# 08_-_CPU_USB.net
KiCad netlist of a schematic drawn in Altium Designer
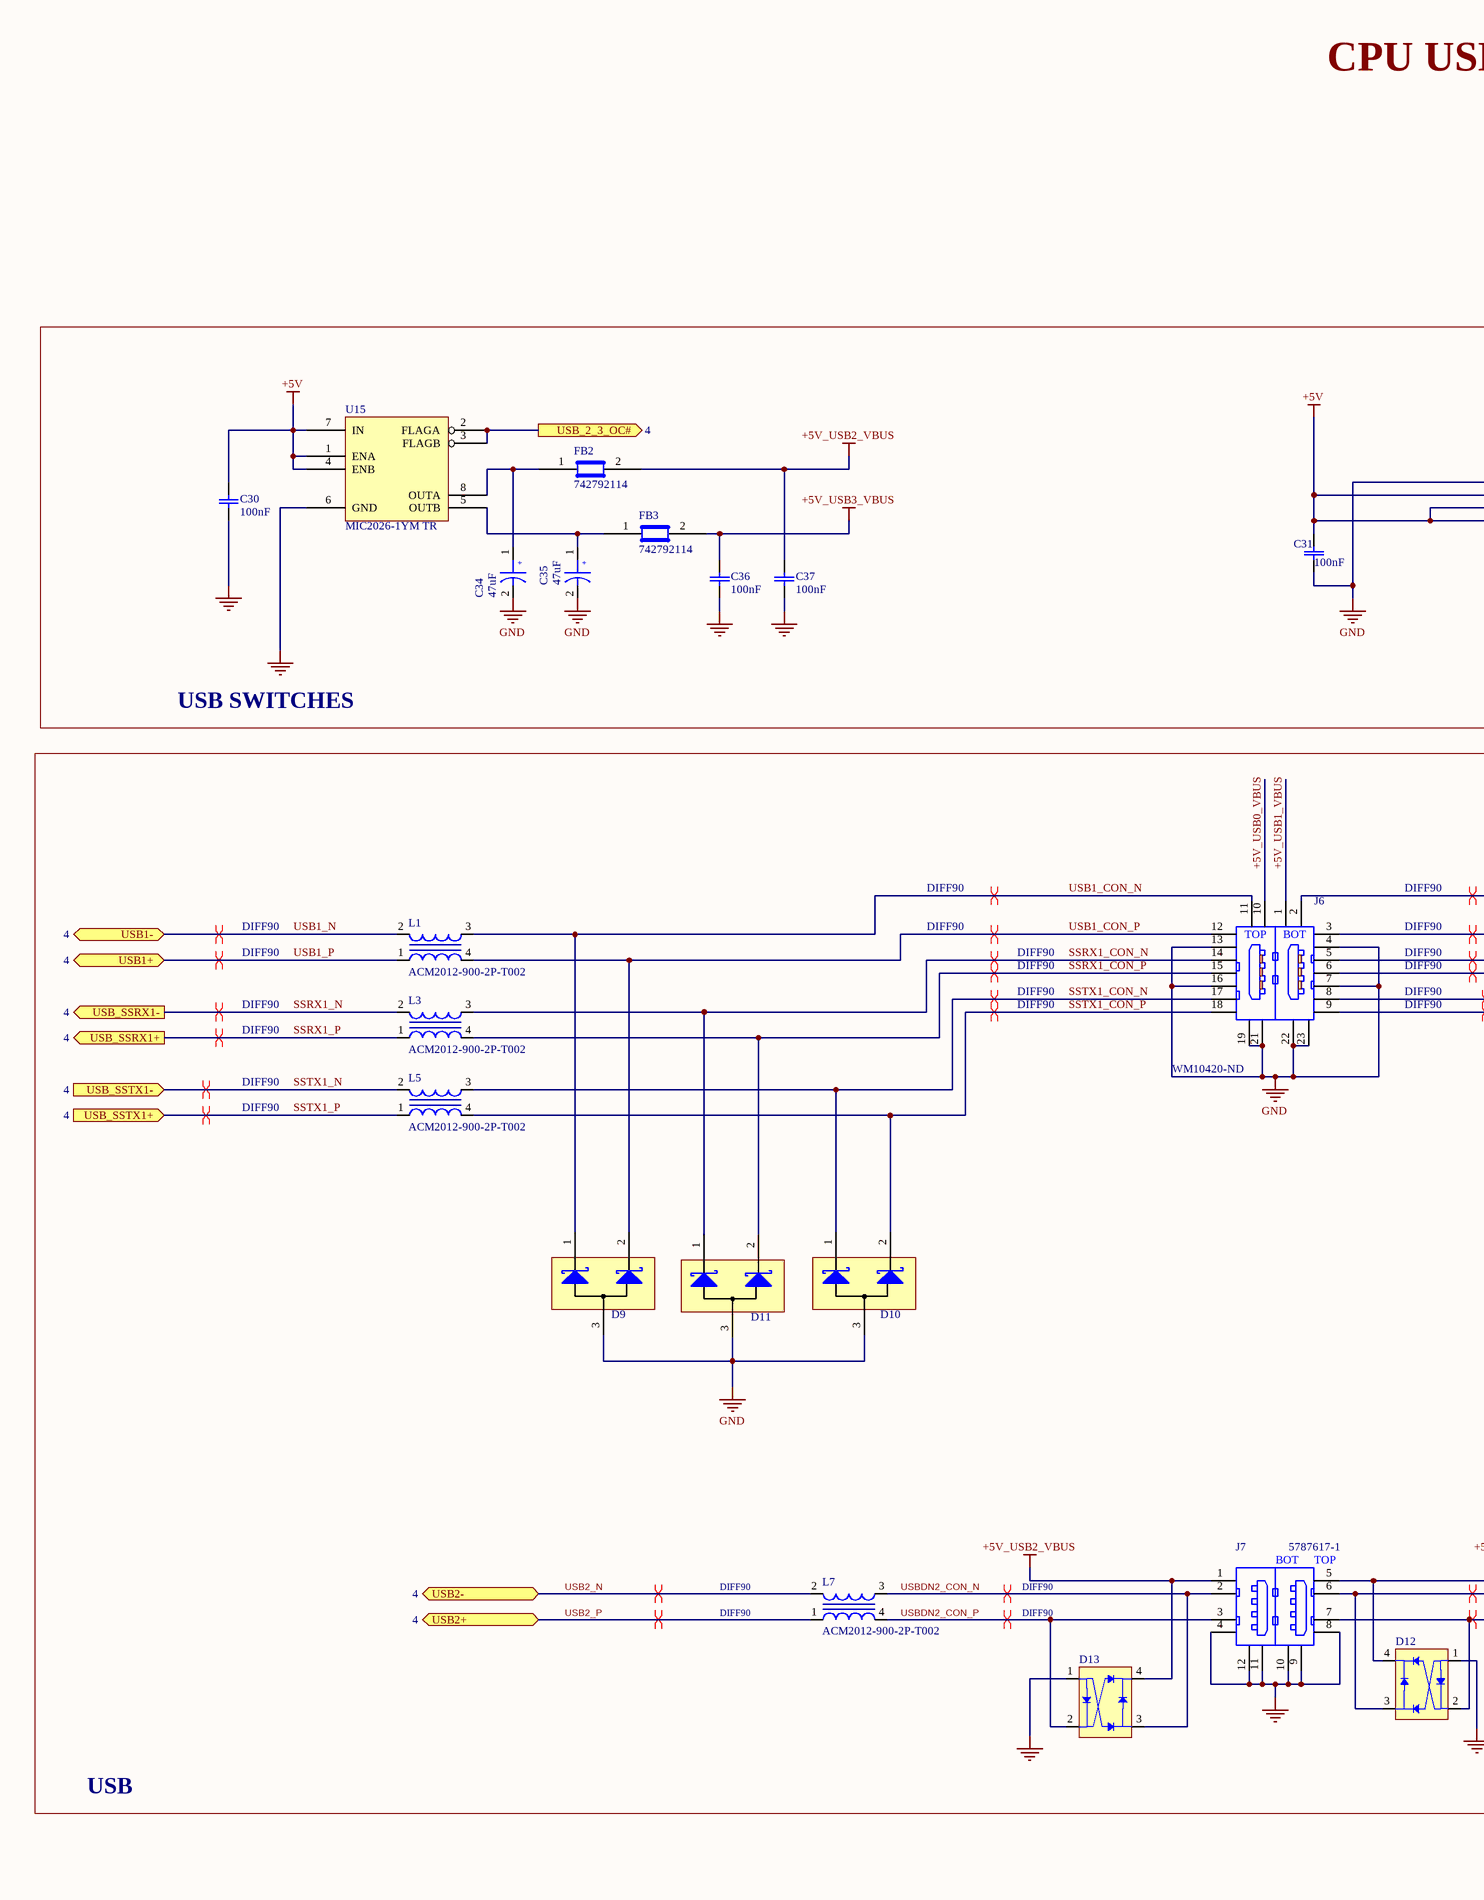
[diagram p0: [08] - CPU USB.SchDoc, left]
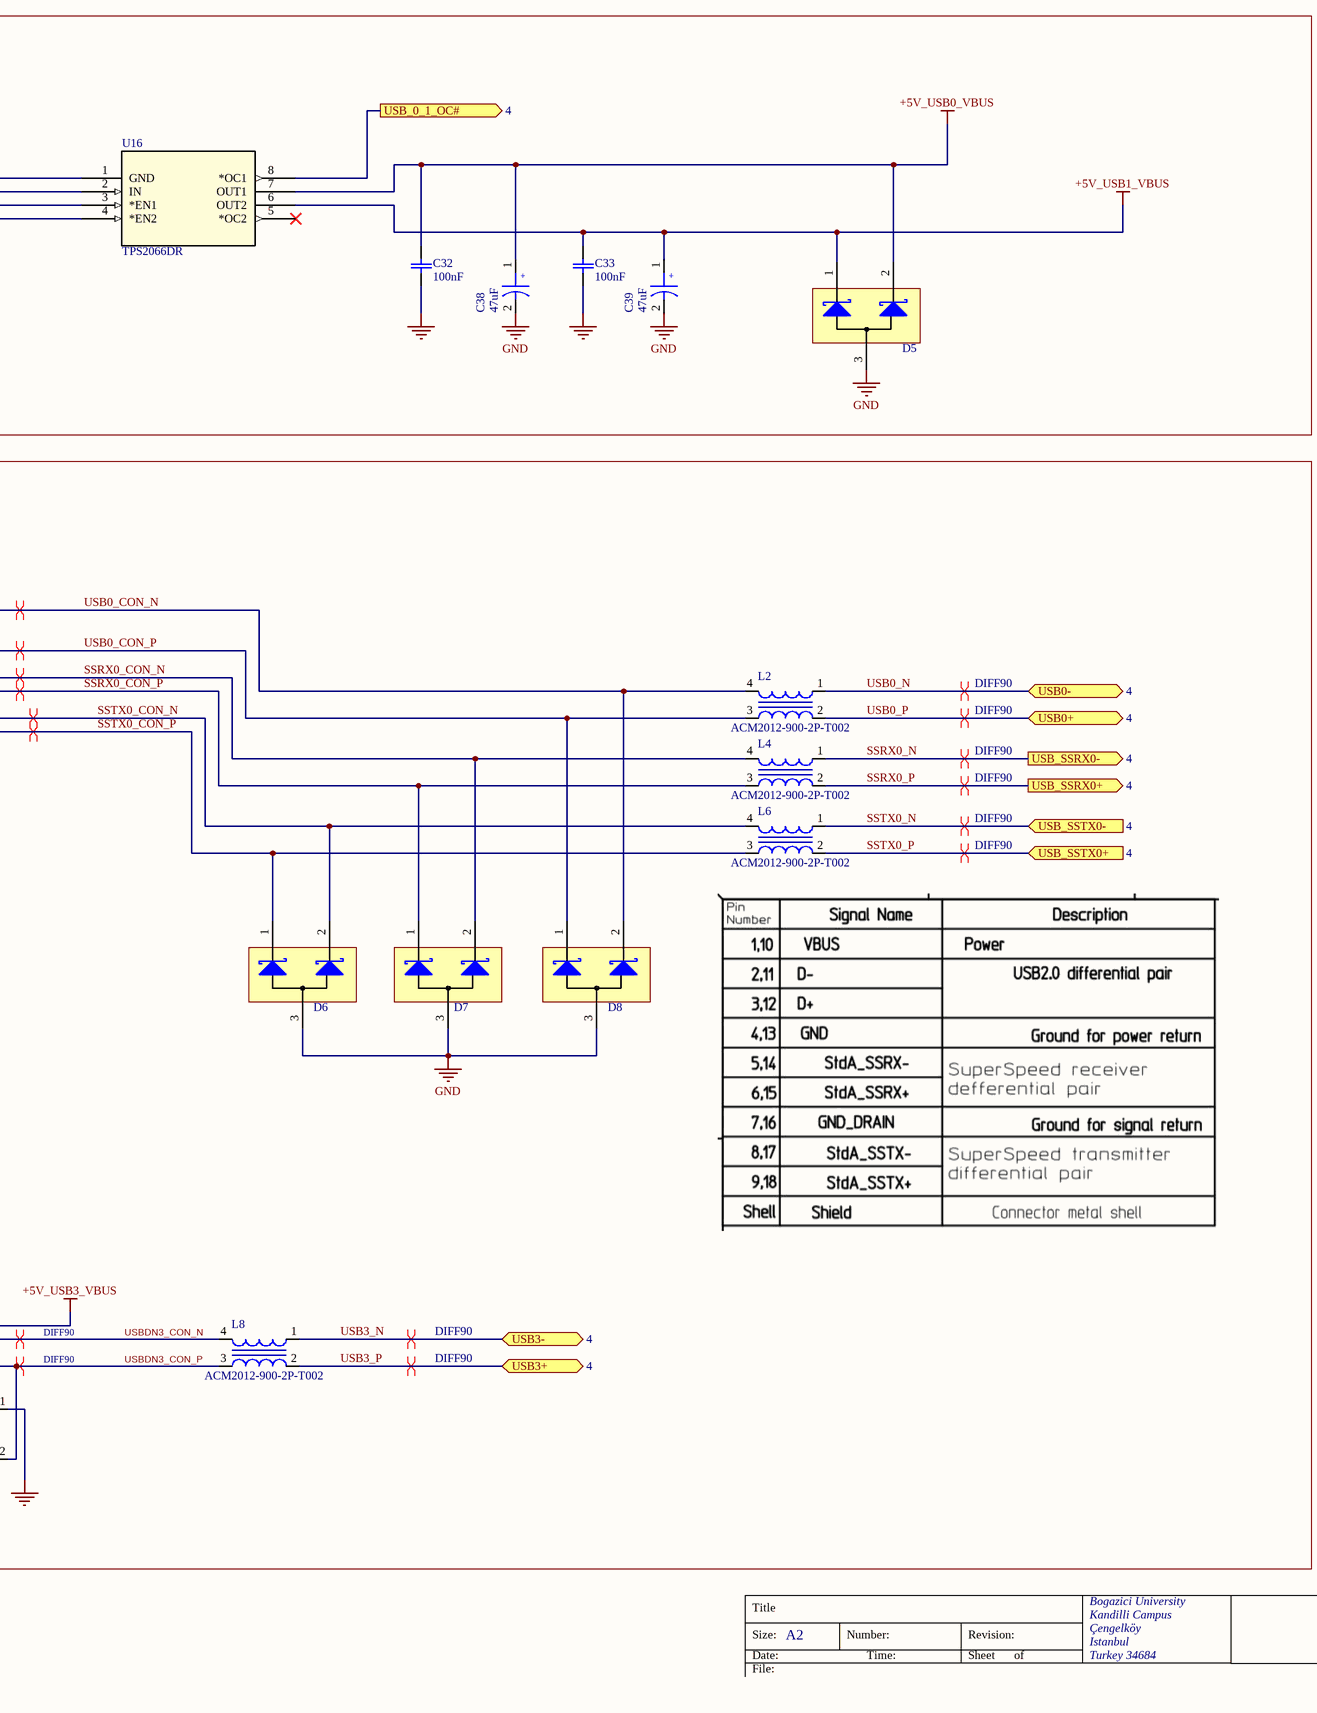
[diagram p1: [08] - CPU USB.SchDoc, right]

(export (version "E")
  (design (tool "Eeschema 10.0.6"))
  (components
    (comp (ref "C30")
      (value "100nF")
      (footprint "C0402")
      (description "CAP CER 0.1UF 50V X8R 0603")
      (fields (field (name "TOLERANCE") "±10%"))
      (libsource (lib "SYNCBOX_V3I1") (part "CL05A104KA5NNNC"))
    )
    (comp (ref "C31")
      (value "100nF")
      (footprint "C0402")
      (description "CAP CER 0.1UF 50V X8R 0603")
      (fields (field (name "TOLERANCE") "±10%"))
      (libsource (lib "SYNCBOX_V3I1") (part "CL05A104KA5NNNC"))
    )
    (comp (ref "C32")
      (value "100nF")
      (footprint "C0402")
      (description "CAP CER 0.1UF 50V X8R 0603")
      (fields (field (name "TOLERANCE") "±10%"))
      (libsource (lib "SYNCBOX_V3I1") (part "CL05A104KA5NNNC"))
    )
    (comp (ref "C33")
      (value "100nF")
      (footprint "C0402")
      (description "CAP CER 0.1UF 50V X8R 0603")
      (fields (field (name "TOLERANCE") "±10%"))
      (libsource (lib "SYNCBOX_V3I1") (part "CL05A104KA5NNNC"))
    )
    (comp (ref "C34")
      (value "47uF")
      (footprint "CAP_P-B")
      (description "CAP ALUM POLY 47UF 20% 16V SMD")
      (fields (field (name "TOLERANCE") "±20%"))
      (libsource (lib "SYNCBOX_V3I1") (part "PCG1C470MCL1GS"))
    )
    (comp (ref "C35")
      (value "47uF")
      (footprint "CAP_P-B")
      (description "CAP ALUM POLY 47UF 20% 16V SMD")
      (fields (field (name "TOLERANCE") "±20%"))
      (libsource (lib "SYNCBOX_V3I1") (part "PCG1C470MCL1GS"))
    )
    (comp (ref "C36")
      (value "100nF")
      (footprint "C0402")
      (description "CAP CER 0.1UF 50V X8R 0603")
      (fields (field (name "TOLERANCE") "±10%"))
      (libsource (lib "SYNCBOX_V3I1") (part "CL05A104KA5NNNC"))
    )
    (comp (ref "C37")
      (value "100nF")
      (footprint "C0402")
      (description "CAP CER 0.1UF 50V X8R 0603")
      (fields (field (name "TOLERANCE") "±10%"))
      (libsource (lib "SYNCBOX_V3I1") (part "CL05A104KA5NNNC"))
    )
    (comp (ref "C38")
      (value "47uF")
      (footprint "CAP_P-B")
      (description "CAP ALUM POLY 47UF 20% 16V SMD")
      (fields (field (name "TOLERANCE") "±20%"))
      (libsource (lib "SYNCBOX_V3I1") (part "PCG1C470MCL1GS"))
    )
    (comp (ref "C39")
      (value "47uF")
      (footprint "CAP_P-B")
      (description "CAP ALUM POLY 47UF 20% 16V SMD")
      (fields (field (name "TOLERANCE") "±20%"))
      (libsource (lib "SYNCBOX_V3I1") (part "PCG1C470MCL1GS"))
    )
    (comp (ref "D5")
      (value "ESD5V3U2U03FH6327XTSA1")
      (footprint "PG-TSLP-3-7")
      (description "TVS DIODE 5.3V 15V TSFP-3")
      (fields (field (name "BASE PART NUMBER") "ESD5V3"))
      (libsource (lib "SYNCBOX_V3I1") (part "ESD5V3U2U03FH6327XTSA1"))
    )
    (comp (ref "D6")
      (value "ESD5V3U2U03FH6327XTSA1")
      (footprint "PG-TSLP-3-7")
      (description "TVS DIODE 5.3V 15V TSFP-3")
      (fields (field (name "BASE PART NUMBER") "ESD5V3"))
      (libsource (lib "SYNCBOX_V3I1") (part "ESD5V3U2U03FH6327XTSA1"))
    )
    (comp (ref "D7")
      (value "ESD5V3U2U03FH6327XTSA1")
      (footprint "PG-TSLP-3-7")
      (description "TVS DIODE 5.3V 15V TSFP-3")
      (fields (field (name "BASE PART NUMBER") "ESD5V3"))
      (libsource (lib "SYNCBOX_V3I1") (part "ESD5V3U2U03FH6327XTSA1"))
    )
    (comp (ref "D8")
      (value "ESD5V3U2U03FH6327XTSA1")
      (footprint "PG-TSLP-3-7")
      (description "TVS DIODE 5.3V 15V TSFP-3")
      (fields (field (name "BASE PART NUMBER") "ESD5V3"))
      (libsource (lib "SYNCBOX_V3I1") (part "ESD5V3U2U03FH6327XTSA1"))
    )
    (comp (ref "D9")
      (value "ESD5V3U2U03FH6327XTSA1")
      (footprint "PG-TSLP-3-7")
      (description "TVS DIODE 5.3V 15V TSFP-3")
      (fields (field (name "BASE PART NUMBER") "ESD5V3"))
      (libsource (lib "SYNCBOX_V3I1") (part "ESD5V3U2U03FH6327XTSA1"))
    )
    (comp (ref "D10")
      (value "ESD5V3U2U03FH6327XTSA1")
      (footprint "PG-TSLP-3-7")
      (description "TVS DIODE 5.3V 15V TSFP-3")
      (fields (field (name "BASE PART NUMBER") "ESD5V3"))
      (libsource (lib "SYNCBOX_V3I1") (part "ESD5V3U2U03FH6327XTSA1"))
    )
    (comp (ref "D11")
      (value "ESD5V3U2U03FH6327XTSA1")
      (footprint "PG-TSLP-3-7")
      (description "TVS DIODE 5.3V 15V TSFP-3")
      (fields (field (name "BASE PART NUMBER") "ESD5V3"))
      (libsource (lib "SYNCBOX_V3I1") (part "ESD5V3U2U03FH6327XTSA1"))
    )
    (comp (ref "D12")
      (value "BAS4002ARPPE6327HTSA1")
      (footprint "SOT143B")
      (description "DIODE BRIDGE 40V 200MA SOT 143")
      (fields (field (name "BASE PART NUMBER") "BAS4002"))
      (libsource (lib "") (part "BAS4002ARPPE6327HTSA1_1"))
    )
    (comp (ref "D13")
      (value "BAS4002ARPPE6327HTSA1")
      (footprint "SOT143B")
      (description "DIODE BRIDGE 40V 200MA SOT 143")
      (fields (field (name "BASE PART NUMBER") "BAS4002"))
      (libsource (lib "SYNCBOX_V3I1") (part "BAS4002ARPPE6327HTSA1"))
    )
    (comp (ref "FB2")
      (value "742792114")
      (footprint "Ferrite bead")
      (description "FERRITE BEAD 50 OHM 1206 1LN")
      (libsource (lib "SYNCBOX_V3I1") (part "FB742792114"))
    )
    (comp (ref "FB3")
      (value "742792114")
      (footprint "Ferrite bead")
      (description "FERRITE BEAD 50 OHM 1206 1LN")
      (libsource (lib "SYNCBOX_V3I1") (part "FB742792114"))
    )
    (comp (ref "J6")
      (value "WM10420-ND")
      (footprint "USB 3 STACK")
      (description "USB 3.0 RA DUAL REC TH TYPE A")
      (libsource (lib "SYNCBOX_V3I1") (part "USB 3"))
    )
    (comp (ref "J7")
      (value "5787617-1")
      (footprint "USB-2A")
      (description "CONN RCPT R/A 4OVER4POS GOLD PCB")
      (fields (field (name "MANUFACTURER") "TE Connectivity"))
      (libsource (lib "SYNCBOX_V3I1") (part "5787617-1"))
    )
    (comp (ref "L1")
      (value "ACM2012-900-2P-T002")
      (footprint "iMX6 Rex Development Baseboard V1I1_PCB:ACM2012")
      (description "CHOKE COMM MODE 90 OHM .4A SMD")
      (fields (field (name "MANUFACTURER") "TDK Corporation") (field (name "TOLERANCE") "±1%"))
      (libsource (lib "SYNCBOX_V3I1") (part "ACM2012-900-2P-T002"))
    )
    (comp (ref "L2")
      (value "ACM2012-900-2P-T002")
      (footprint "iMX6 Rex Development Baseboard V1I1_PCB:ACM2012")
      (description "CHOKE COMM MODE 90 OHM .4A SMD")
      (fields (field (name "MANUFACTURER") "TDK Corporation") (field (name "TOLERANCE") "±1%"))
      (libsource (lib "SYNCBOX_V3I1") (part "ACM2012-900-2P-T002"))
    )
    (comp (ref "L3")
      (value "ACM2012-900-2P-T002")
      (footprint "iMX6 Rex Development Baseboard V1I1_PCB:ACM2012")
      (description "CHOKE COMM MODE 90 OHM .4A SMD")
      (fields (field (name "MANUFACTURER") "TDK Corporation") (field (name "TOLERANCE") "±1%"))
      (libsource (lib "SYNCBOX_V3I1") (part "ACM2012-900-2P-T002"))
    )
    (comp (ref "L4")
      (value "ACM2012-900-2P-T002")
      (footprint "iMX6 Rex Development Baseboard V1I1_PCB:ACM2012")
      (description "CHOKE COMM MODE 90 OHM .4A SMD")
      (fields (field (name "MANUFACTURER") "TDK Corporation") (field (name "TOLERANCE") "±1%"))
      (libsource (lib "SYNCBOX_V3I1") (part "ACM2012-900-2P-T002"))
    )
    (comp (ref "L5")
      (value "ACM2012-900-2P-T002")
      (footprint "iMX6 Rex Development Baseboard V1I1_PCB:ACM2012")
      (description "CHOKE COMM MODE 90 OHM .4A SMD")
      (fields (field (name "MANUFACTURER") "TDK Corporation") (field (name "TOLERANCE") "±1%"))
      (libsource (lib "SYNCBOX_V3I1") (part "ACM2012-900-2P-T002"))
    )
    (comp (ref "L6")
      (value "ACM2012-900-2P-T002")
      (footprint "iMX6 Rex Development Baseboard V1I1_PCB:ACM2012")
      (description "CHOKE COMM MODE 90 OHM .4A SMD")
      (fields (field (name "MANUFACTURER") "TDK Corporation") (field (name "TOLERANCE") "±1%"))
      (libsource (lib "SYNCBOX_V3I1") (part "ACM2012-900-2P-T002"))
    )
    (comp (ref "L7")
      (value "ACM2012-900-2P-T002")
      (footprint "iMX6 Rex Development Baseboard V1I1_PCB:ACM2012")
      (description "CHOKE COMM MODE 90 OHM .4A SMD")
      (fields (field (name "MANUFACTURER") "TDK Corporation") (field (name "TOLERANCE") "±1%"))
      (libsource (lib "SYNCBOX_V3I1") (part "ACM2012-900-2P-T002"))
    )
    (comp (ref "L8")
      (value "ACM2012-900-2P-T002")
      (footprint "iMX6 Rex Development Baseboard V1I1_PCB:ACM2012")
      (description "CHOKE COMM MODE 90 OHM .4A SMD")
      (fields (field (name "MANUFACTURER") "TDK Corporation") (field (name "TOLERANCE") "±1%"))
      (libsource (lib "SYNCBOX_V3I1") (part "ACM2012-900-2P-T002"))
    )
    (comp (ref "U15")
      (value "MIC2026-1YM TR")
      (footprint "8_SOIC_3.9MM")
      (description "IC SW DISTRIBUTION 2CHAN 8SOIC")
      (fields (field (name "MANUFACTURER") "Micrel Inc"))
      (libsource (lib "SYNCBOX_V3I1") (part "MIC2026-1YM TR"))
    )
    (comp (ref "U16")
      (value "TPS2066DR")
      (footprint "D8")
      (description "IC PWR DIST SW DUAL 8SOIC")
      (fields (field (name "MANUFACTURER") "Texas Instruments") (field (name "BASE PART NUMBER") "TPS2066"))
      (libsource (lib "SYNCBOX_V3I1") (part "TPS2066DR"))
    )
  )
  (nets
    (net (code "1") (name "+5V") (class "Default")
      (node (ref "C30") (pin "2") (pinfunction "2_2") (pintype "passive"))
      (node (ref "C31") (pin "2") (pinfunction "2_2") (pintype "passive"))
      (node (ref "U15") (pin "1") (pinfunction "ENA_1") (pintype "passive"))
      (node (ref "U15") (pin "4") (pinfunction "ENB_4") (pintype "passive"))
      (node (ref "U15") (pin "7") (pinfunction "IN_7") (pintype "power_in"))
      (node (ref "U16") (pin "2") (pinfunction "IN_2") (pintype "input"))
      (node (ref "U16") (pin "3") (pinfunction "*EN1_3") (pintype "input"))
      (node (ref "U16") (pin "4") (pinfunction "*EN2_4") (pintype "input"))
    )
    (net (code "2") (name "+5V_USB0_VBUS") (class "Default")
      (node (ref "C32") (pin "2") (pinfunction "2_2") (pintype "passive"))
      (node (ref "C38") (pin "1") (pinfunction "1_1") (pintype "passive"))
      (node (ref "D5") (pin "2") (pinfunction "2_2") (pintype "passive"))
      (node (ref "J6") (pin "10") (pinfunction "VBUS2_10") (pintype "power_in"))
      (node (ref "U16") (pin "7") (pinfunction "OUT1_7") (pintype "power_in"))
    )
    (net (code "3") (name "+5V_USB1_VBUS") (class "Default")
      (node (ref "C33") (pin "2") (pinfunction "2_2") (pintype "passive"))
      (node (ref "C39") (pin "1") (pinfunction "1_1") (pintype "passive"))
      (node (ref "D5") (pin "1") (pinfunction "1_1") (pintype "passive"))
      (node (ref "J6") (pin "1") (pinfunction "VBUS1_1") (pintype "power_in"))
      (node (ref "U16") (pin "6") (pinfunction "OUT2_6") (pintype "power_in"))
    )
    (net (code "4") (name "+5V_USB2_VBUS") (class "Default")
      (node (ref "C37") (pin "2") (pinfunction "2_2") (pintype "passive"))
      (node (ref "D13") (pin "4") (pinfunction "4_4") (pintype "passive"))
      (node (ref "FB2") (pin "2") (pinfunction "2_2") (pintype "passive"))
      (node (ref "J7") (pin "1") (pinfunction "VBUS_1") (pintype "passive"))
    )
    (net (code "5") (name "+5V_USB3_VBUS") (class "Default")
      (node (ref "C36") (pin "2") (pinfunction "2_2") (pintype "passive"))
      (node (ref "D12") (pin "4") (pinfunction "4_4") (pintype "passive"))
      (node (ref "FB3") (pin "2") (pinfunction "2_2") (pintype "passive"))
      (node (ref "J7") (pin "5") (pinfunction "VBUS2_5") (pintype "passive"))
    )
    (net (code "6") (name "/SSRX0_CON_N") (class "Default")
      (node (ref "D7") (pin "2") (pinfunction "2_2") (pintype "passive"))
      (node (ref "J6") (pin "5") (pinfunction "SSRX0-_5") (pintype "passive"))
      (node (ref "L4") (pin "4") (pinfunction "4_4") (pintype "passive"))
    )
    (net (code "7") (name "/SSRX0_CON_P") (class "Default")
      (node (ref "D7") (pin "1") (pinfunction "1_1") (pintype "passive"))
      (node (ref "J6") (pin "6") (pinfunction "SSRX0+_6") (pintype "passive"))
      (node (ref "L4") (pin "3") (pinfunction "3_3") (pintype "passive"))
    )
    (net (code "8") (name "/SSRX0_N") (class "Default")
      (node (ref "L4") (pin "1") (pinfunction "1_1") (pintype "passive"))
    )
    (net (code "9") (name "/SSRX0_P") (class "Default")
      (node (ref "L4") (pin "2") (pinfunction "2_2") (pintype "passive"))
    )
    (net (code "10") (name "/SSRX1_CON_N") (class "Default")
      (node (ref "D11") (pin "1") (pinfunction "1_1") (pintype "passive"))
      (node (ref "J6") (pin "14") (pinfunction "SSRX2-_14") (pintype "passive"))
      (node (ref "L3") (pin "3") (pinfunction "3_3") (pintype "passive"))
    )
    (net (code "11") (name "/SSRX1_CON_P") (class "Default")
      (node (ref "D11") (pin "2") (pinfunction "2_2") (pintype "passive"))
      (node (ref "J6") (pin "15") (pinfunction "SSRX2+_15") (pintype "passive"))
      (node (ref "L3") (pin "4") (pinfunction "4_4") (pintype "passive"))
    )
    (net (code "12") (name "/SSRX1_N") (class "Default")
      (node (ref "L3") (pin "2") (pinfunction "2_2") (pintype "passive"))
    )
    (net (code "13") (name "/SSRX1_P") (class "Default")
      (node (ref "L3") (pin "1") (pinfunction "1_1") (pintype "passive"))
    )
    (net (code "14") (name "/SSTX0_CON_N") (class "Default")
      (node (ref "D6") (pin "2") (pinfunction "2_2") (pintype "passive"))
      (node (ref "J6") (pin "8") (pinfunction "SSTX0-_8") (pintype "passive"))
      (node (ref "L6") (pin "4") (pinfunction "4_4") (pintype "passive"))
    )
    (net (code "15") (name "/SSTX0_CON_P") (class "Default")
      (node (ref "D6") (pin "1") (pinfunction "1_1") (pintype "passive"))
      (node (ref "J6") (pin "9") (pinfunction "SSTX0+_9") (pintype "passive"))
      (node (ref "L6") (pin "3") (pinfunction "3_3") (pintype "passive"))
    )
    (net (code "16") (name "/SSTX0_N") (class "Default")
      (node (ref "L6") (pin "1") (pinfunction "1_1") (pintype "passive"))
    )
    (net (code "17") (name "/SSTX0_P") (class "Default")
      (node (ref "L6") (pin "2") (pinfunction "2_2") (pintype "passive"))
    )
    (net (code "18") (name "/SSTX1_CON_N") (class "Default")
      (node (ref "D10") (pin "1") (pinfunction "1_1") (pintype "passive"))
      (node (ref "J6") (pin "17") (pinfunction "SSTX2-_17") (pintype "passive"))
      (node (ref "L5") (pin "3") (pinfunction "3_3") (pintype "passive"))
    )
    (net (code "19") (name "/SSTX1_CON_P") (class "Default")
      (node (ref "D10") (pin "2") (pinfunction "2_2") (pintype "passive"))
      (node (ref "J6") (pin "18") (pinfunction "SSTX2+_18") (pintype "passive"))
      (node (ref "L5") (pin "4") (pinfunction "4_4") (pintype "passive"))
    )
    (net (code "20") (name "/SSTX1_N") (class "Default")
      (node (ref "L5") (pin "2") (pinfunction "2_2") (pintype "passive"))
    )
    (net (code "21") (name "/SSTX1_P") (class "Default")
      (node (ref "L5") (pin "1") (pinfunction "1_1") (pintype "passive"))
    )
    (net (code "22") (name "/USB0_CON_N") (class "Default")
      (node (ref "D8") (pin "2") (pinfunction "2_2") (pintype "passive"))
      (node (ref "J6") (pin "2") (pinfunction "D1-_2") (pintype "passive"))
      (node (ref "L2") (pin "4") (pinfunction "4_4") (pintype "passive"))
    )
    (net (code "23") (name "/USB0_CON_P") (class "Default")
      (node (ref "D8") (pin "1") (pinfunction "1_1") (pintype "passive"))
      (node (ref "J6") (pin "3") (pinfunction "D1+_3") (pintype "passive"))
      (node (ref "L2") (pin "3") (pinfunction "3_3") (pintype "passive"))
    )
    (net (code "24") (name "/USB0_N") (class "Default")
      (node (ref "L2") (pin "1") (pinfunction "1_1") (pintype "passive"))
    )
    (net (code "25") (name "/USB0_P") (class "Default")
      (node (ref "L2") (pin "2") (pinfunction "2_2") (pintype "passive"))
    )
    (net (code "26") (name "/USB1_CON_N") (class "Default")
      (node (ref "D9") (pin "1") (pinfunction "1_1") (pintype "passive"))
      (node (ref "J6") (pin "11") (pinfunction "D2-_11") (pintype "passive"))
      (node (ref "L1") (pin "3") (pinfunction "3_3") (pintype "passive"))
    )
    (net (code "27") (name "/USB1_CON_P") (class "Default")
      (node (ref "D9") (pin "2") (pinfunction "2_2") (pintype "passive"))
      (node (ref "J6") (pin "12") (pinfunction "D2+_12") (pintype "passive"))
      (node (ref "L1") (pin "4") (pinfunction "4_4") (pintype "passive"))
    )
    (net (code "28") (name "/USB1_N") (class "Default")
      (node (ref "L1") (pin "2") (pinfunction "2_2") (pintype "passive"))
    )
    (net (code "29") (name "/USB1_P") (class "Default")
      (node (ref "L1") (pin "1") (pinfunction "1_1") (pintype "passive"))
    )
    (net (code "30") (name "/USB2_N") (class "Default")
      (node (ref "L7") (pin "2") (pinfunction "2_2") (pintype "passive"))
    )
    (net (code "31") (name "/USB2_P") (class "Default")
      (node (ref "L7") (pin "1") (pinfunction "1_1") (pintype "passive"))
    )
    (net (code "32") (name "/USB3_N") (class "Default")
      (node (ref "L8") (pin "1") (pinfunction "1_1") (pintype "passive"))
    )
    (net (code "33") (name "/USB3_P") (class "Default")
      (node (ref "L8") (pin "2") (pinfunction "2_2") (pintype "passive"))
    )
    (net (code "34") (name "/USBDN2_CON_N") (class "Default")
      (node (ref "D13") (pin "3") (pinfunction "3_3") (pintype "passive"))
      (node (ref "J7") (pin "2") (pinfunction "D-_2") (pintype "passive"))
      (node (ref "L7") (pin "3") (pinfunction "3_3") (pintype "passive"))
    )
    (net (code "35") (name "/USBDN2_CON_P") (class "Default")
      (node (ref "D13") (pin "2") (pinfunction "2_2") (pintype "passive"))
      (node (ref "J7") (pin "3") (pinfunction "D+_3") (pintype "passive"))
      (node (ref "L7") (pin "4") (pinfunction "4_4") (pintype "passive"))
    )
    (net (code "36") (name "/USBDN3_CON_N") (class "Default")
      (node (ref "D12") (pin "3") (pinfunction "3_3") (pintype "passive"))
      (node (ref "J7") (pin "6") (pinfunction "D2-_6") (pintype "passive"))
      (node (ref "L8") (pin "4") (pinfunction "4_4") (pintype "passive"))
    )
    (net (code "37") (name "/USBDN3_CON_P") (class "Default")
      (node (ref "D12") (pin "2") (pinfunction "2_2") (pintype "passive"))
      (node (ref "J7") (pin "7") (pinfunction "D2+_7") (pintype "passive"))
      (node (ref "L8") (pin "3") (pinfunction "3_3") (pintype "passive"))
    )
    (net (code "38") (name "/USB_0_1_OC#") (class "Default")
      (node (ref "U16") (pin "8") (pinfunction "*OC1_8") (pintype "output"))
    )
    (net (code "39") (name "/USB_2_3_OC#") (class "Default")
      (node (ref "U15") (pin "2") (pinfunction "FLAGA_2") (pintype "passive"))
      (node (ref "U15") (pin "3") (pinfunction "FLAGB_3") (pintype "passive"))
    )
    (net (code "40") (name "GND") (class "Default")
      (node (ref "C30") (pin "1") (pinfunction "1_1") (pintype "passive"))
      (node (ref "C31") (pin "1") (pinfunction "1_1") (pintype "passive"))
      (node (ref "C32") (pin "1") (pinfunction "1_1") (pintype "passive"))
      (node (ref "C33") (pin "1") (pinfunction "1_1") (pintype "passive"))
      (node (ref "C34") (pin "2") (pinfunction "2_2") (pintype "passive"))
      (node (ref "C35") (pin "2") (pinfunction "2_2") (pintype "passive"))
      (node (ref "C36") (pin "1") (pinfunction "1_1") (pintype "passive"))
      (node (ref "C37") (pin "1") (pinfunction "1_1") (pintype "passive"))
      (node (ref "C38") (pin "2") (pinfunction "2_2") (pintype "passive"))
      (node (ref "C39") (pin "2") (pinfunction "2_2") (pintype "passive"))
      (node (ref "D10") (pin "3") (pinfunction "3_3") (pintype "passive"))
      (node (ref "D11") (pin "3") (pinfunction "3_3") (pintype "passive"))
      (node (ref "D12") (pin "1") (pinfunction "1_1") (pintype "passive"))
      (node (ref "D13") (pin "1") (pinfunction "1_1") (pintype "passive"))
      (node (ref "D5") (pin "3") (pinfunction "3_3") (pintype "passive"))
      (node (ref "D6") (pin "3") (pinfunction "3_3") (pintype "passive"))
      (node (ref "D7") (pin "3") (pinfunction "3_3") (pintype "passive"))
      (node (ref "D8") (pin "3") (pinfunction "3_3") (pintype "passive"))
      (node (ref "D9") (pin "3") (pinfunction "3_3") (pintype "passive"))
      (node (ref "J6") (pin "13") (pinfunction "GND_13") (pintype "power_in"))
      (node (ref "J6") (pin "16") (pinfunction "GND_DRAIN2_16") (pintype "passive"))
      (node (ref "J6") (pin "19") (pinfunction "SHIELD_19") (pintype "passive"))
      (node (ref "J6") (pin "21") (pinfunction "SHIELD_21") (pintype "passive"))
      (node (ref "J6") (pin "22") (pinfunction "SHIELD_22") (pintype "passive"))
      (node (ref "J6") (pin "23") (pinfunction "SHIELD_23") (pintype "passive"))
      (node (ref "J6") (pin "4") (pinfunction "GND_4") (pintype "power_in"))
      (node (ref "J6") (pin "7") (pinfunction "GND_DRAIN1_7") (pintype "passive"))
      (node (ref "J7") (pin "10") (pinfunction "SHIELD_10") (pintype "passive"))
      (node (ref "J7") (pin "11") (pinfunction "SHIELD_11") (pintype "passive"))
      (node (ref "J7") (pin "12") (pinfunction "SHIELD_12") (pintype "passive"))
      (node (ref "J7") (pin "4") (pinfunction "GND_4") (pintype "passive"))
      (node (ref "J7") (pin "8") (pinfunction "GND_8") (pintype "passive"))
      (node (ref "J7") (pin "9") (pinfunction "SHIELD_9") (pintype "passive"))
      (node (ref "U15") (pin "6") (pinfunction "GND_6") (pintype "power_in"))
      (node (ref "U16") (pin "1") (pinfunction "GND_1") (pintype "power_in"))
    )
    (net (code "41") (name "Net-(U15-OUTA)") (class "Default")
      (node (ref "C34") (pin "1") (pinfunction "1_1") (pintype "passive"))
      (node (ref "FB2") (pin "1") (pinfunction "1_1") (pintype "passive"))
      (node (ref "U15") (pin "8") (pinfunction "OUTA_8") (pintype "passive"))
    )
    (net (code "42") (name "Net-(U15-OUTB)") (class "Default")
      (node (ref "C35") (pin "1") (pinfunction "1_1") (pintype "passive"))
      (node (ref "FB3") (pin "1") (pinfunction "1_1") (pintype "passive"))
      (node (ref "U15") (pin "5") (pinfunction "OUTB_5") (pintype "passive"))
    )
    (net (code "43") (name "unconnected-(U16-*OC2-Pad5)") (class "Default")
      (node (ref "U16") (pin "5") (pinfunction "*OC2_5") (pintype "output+no_connect"))
    )
  )
)
